# SolarController.net
KiCad netlist of a schematic drawn in EAGLE
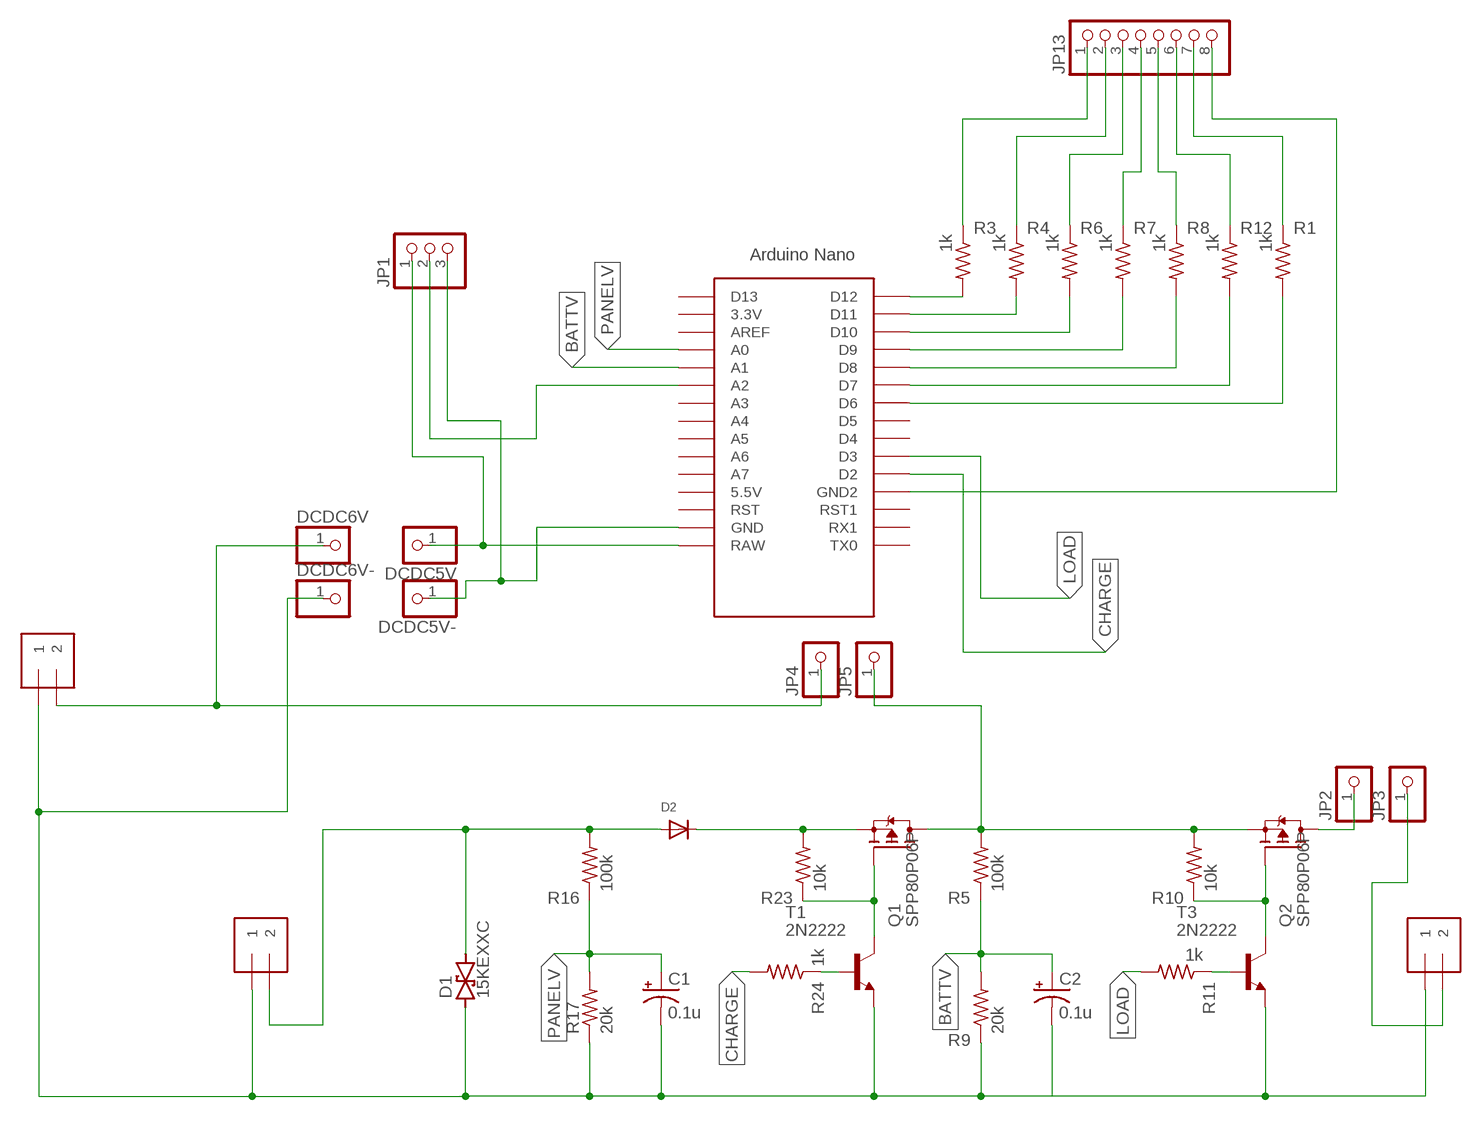
[diagram p0: schematic, sheet 1]

(export (version "E")
  (design (tool "Eeschema 10.0.6"))
  (components
    (comp (ref "BATTERY")
      (value "1X2-3.5MM")
      (footprint "eagle-import:1X2-3.5MM")
      (libsource (lib "eagle-import") (part "1X2-3.5MM"))
    )
    (comp (ref "C1")
      (value "0.1u")
      (footprint "eagle-import:B45181B")
      (libsource (lib "eagle-import") (part "CPOL-USB45181B"))
    )
    (comp (ref "C2")
      (value "0.1u")
      (footprint "eagle-import:B45181B")
      (libsource (lib "eagle-import") (part "CPOL-USB45181B"))
    )
    (comp (ref "D1")
      (value "15KEXXC")
      (footprint "eagle-import:CB429-17")
      (libsource (lib "eagle-import") (part "15KEXXC"))
    )
    (comp (ref "D2")
      (value "DIODEDO-1N4148")
      (footprint "eagle-import:DO-1N4148")
      (libsource (lib "eagle-import") (part "DIODEDO-1N4148"))
    )
    (comp (ref "DCDC5V")
      (value "PINHD-1X1CB")
      (footprint "eagle-import:1X01-CLEANBIG")
      (libsource (lib "eagle-import") (part "PINHD-1X1CB"))
    )
    (comp (ref "DCDC5V-")
      (value "PINHD-1X1CB")
      (footprint "eagle-import:1X01-CLEANBIG")
      (libsource (lib "eagle-import") (part "PINHD-1X1CB"))
    )
    (comp (ref "DCDC6V")
      (value "PINHD-1X1CB")
      (footprint "eagle-import:1X01-CLEANBIG")
      (libsource (lib "eagle-import") (part "PINHD-1X1CB"))
    )
    (comp (ref "DCDC6V-")
      (value "PINHD-1X1CB")
      (footprint "eagle-import:1X01-CLEANBIG")
      (libsource (lib "eagle-import") (part "PINHD-1X1CB"))
    )
    (comp (ref "JP1")
      (value "PINHD-1X3CB")
      (footprint "eagle-import:1X03-CLEANBIG")
      (libsource (lib "eagle-import") (part "PINHD-1X3CB"))
    )
    (comp (ref "JP2")
      (value "PINHD-1X1CB")
      (footprint "eagle-import:1X01-CLEANBIG")
      (libsource (lib "eagle-import") (part "PINHD-1X1CB"))
    )
    (comp (ref "JP3")
      (value "PINHD-1X1CB")
      (footprint "eagle-import:1X01-CLEANBIG")
      (libsource (lib "eagle-import") (part "PINHD-1X1CB"))
    )
    (comp (ref "JP4")
      (value "PINHD-1X1CB")
      (footprint "eagle-import:1X01-CLEANBIG")
      (libsource (lib "eagle-import") (part "PINHD-1X1CB"))
    )
    (comp (ref "JP5")
      (value "PINHD-1X1CB")
      (footprint "eagle-import:1X01-CLEANBIG")
      (libsource (lib "eagle-import") (part "PINHD-1X1CB"))
    )
    (comp (ref "JP13")
      (value "PINHD-1X8BIG")
      (footprint "eagle-import:1X08-BIG")
      (libsource (lib "eagle-import") (part "PINHD-1X8BIG"))
    )
    (comp (ref "LOAD")
      (value "1X2-3.5MM")
      (footprint "eagle-import:1X2-3.5MM")
      (libsource (lib "eagle-import") (part "1X2-3.5MM"))
    )
    (comp (ref "PANEL")
      (value "1X2-3.5MM")
      (footprint "eagle-import:1X2-3.5MM")
      (libsource (lib "eagle-import") (part "1X2-3.5MM"))
    )
    (comp (ref "Q1")
      (value "SPP80P06P")
      (footprint "eagle-import:TO220")
      (libsource (lib "eagle-import") (part "SPP80P06P"))
    )
    (comp (ref "Q2")
      (value "SPP80P06P")
      (footprint "eagle-import:TO220")
      (libsource (lib "eagle-import") (part "SPP80P06P"))
    )
    (comp (ref "R1")
      (value "1k")
      (footprint "eagle-import:0207_9")
      (libsource (lib "eagle-import") (part "R-US_0207/9"))
    )
    (comp (ref "R3")
      (value "1k")
      (footprint "eagle-import:0207_9")
      (libsource (lib "eagle-import") (part "R-US_0207/9"))
    )
    (comp (ref "R4")
      (value "1k")
      (footprint "eagle-import:0207_9")
      (libsource (lib "eagle-import") (part "R-US_0207/9"))
    )
    (comp (ref "R5")
      (value "100k")
      (footprint "eagle-import:0207_9")
      (libsource (lib "eagle-import") (part "R-US_0207/9"))
    )
    (comp (ref "R6")
      (value "1k")
      (footprint "eagle-import:0207_9")
      (libsource (lib "eagle-import") (part "R-US_0207/9"))
    )
    (comp (ref "R7")
      (value "1k")
      (footprint "eagle-import:0207_9")
      (libsource (lib "eagle-import") (part "R-US_0207/9"))
    )
    (comp (ref "R8")
      (value "1k")
      (footprint "eagle-import:0207_9")
      (libsource (lib "eagle-import") (part "R-US_0207/9"))
    )
    (comp (ref "R9")
      (value "20k")
      (footprint "eagle-import:0207_9")
      (libsource (lib "eagle-import") (part "R-US_0207/9"))
    )
    (comp (ref "R10")
      (value "10k")
      (footprint "eagle-import:0207_9")
      (libsource (lib "eagle-import") (part "R-US_0207/9"))
    )
    (comp (ref "R11")
      (value "1k")
      (footprint "eagle-import:0207_9")
      (libsource (lib "eagle-import") (part "R-US_0207/9"))
    )
    (comp (ref "R12")
      (value "1k")
      (footprint "eagle-import:0207_9")
      (libsource (lib "eagle-import") (part "R-US_0207/9"))
    )
    (comp (ref "R16")
      (value "100k")
      (footprint "eagle-import:0207_9")
      (libsource (lib "eagle-import") (part "R-US_0207/9"))
    )
    (comp (ref "R17")
      (value "20k")
      (footprint "eagle-import:0207_9")
      (libsource (lib "eagle-import") (part "R-US_0207/9"))
    )
    (comp (ref "R23")
      (value "10k")
      (footprint "eagle-import:0207_9")
      (libsource (lib "eagle-import") (part "R-US_0207/9"))
    )
    (comp (ref "R24")
      (value "1k")
      (footprint "eagle-import:0207_9")
      (libsource (lib "eagle-import") (part "R-US_0207/9"))
    )
    (comp (ref "T1")
      (value "2N2222")
      (footprint "eagle-import:TO92-EBC-OVAL")
      (libsource (lib "eagle-import") (part "2N2222"))
    )
    (comp (ref "T3")
      (value "2N2222")
      (footprint "eagle-import:TO92-EBC-OVAL")
      (libsource (lib "eagle-import") (part "2N2222"))
    )
    (comp (ref "U$1")
      (value "NANO")
      (footprint "eagle-import:NANO")
      (libsource (lib "eagle-import") (part "NANO"))
    )
  )
  (nets
    (net (code "1") (name "BATTV") (class "Default")
      (node (ref "C2") (pin "+") (pinfunction "+_+") (pintype "passive"))
      (node (ref "R5") (pin "1") (pinfunction "1_1") (pintype "passive"))
      (node (ref "R9") (pin "2") (pinfunction "2_2") (pintype "passive"))
      (node (ref "U$1") (pin "A1") (pinfunction "A1_A1") (pintype "bidirectional"))
    )
    (net (code "2") (name "CHARGE") (class "Default")
      (node (ref "R24") (pin "2") (pinfunction "2_2") (pintype "passive"))
      (node (ref "U$1") (pin "D2") (pinfunction "D2_D2") (pintype "bidirectional"))
    )
    (net (code "3") (name "LOAD") (class "Default")
      (node (ref "R11") (pin "2") (pinfunction "2_2") (pintype "passive"))
      (node (ref "U$1") (pin "D3") (pinfunction "D3_D3") (pintype "bidirectional"))
    )
    (net (code "4") (name "Net-(BATTERY-Pad2)") (class "Default")
      (node (ref "BATTERY") (pin "2") (pinfunction "2_2") (pintype "passive"))
      (node (ref "DCDC6V") (pin "1") (pinfunction "1_1") (pintype "passive"))
      (node (ref "JP4") (pin "1") (pinfunction "1_1") (pintype "passive"))
    )
    (net (code "5") (name "Net-(D1-1)") (class "Default")
      (node (ref "BATTERY") (pin "1") (pinfunction "1_1") (pintype "passive"))
      (node (ref "C1") (pin "-") (pinfunction "-_-") (pintype "passive"))
      (node (ref "C2") (pin "-") (pinfunction "-_-") (pintype "passive"))
      (node (ref "D1") (pin "A") (pinfunction "1_A") (pintype "passive"))
      (node (ref "DCDC6V-") (pin "1") (pinfunction "1_1") (pintype "passive"))
      (node (ref "LOAD") (pin "1") (pinfunction "1_1") (pintype "passive"))
      (node (ref "PANEL") (pin "1") (pinfunction "1_1") (pintype "passive"))
      (node (ref "R17") (pin "1") (pinfunction "1_1") (pintype "passive"))
      (node (ref "R9") (pin "1") (pinfunction "1_1") (pintype "passive"))
      (node (ref "T1") (pin "E") (pinfunction "E_E") (pintype "passive"))
      (node (ref "T3") (pin "E") (pinfunction "E_E") (pintype "passive"))
    )
    (net (code "6") (name "Net-(D1-2)") (class "Default")
      (node (ref "D1") (pin "C") (pinfunction "2_C") (pintype "passive"))
      (node (ref "D2") (pin "A") (pinfunction "A_A") (pintype "passive"))
      (node (ref "PANEL") (pin "2") (pinfunction "2_2") (pintype "passive"))
      (node (ref "R16") (pin "2") (pinfunction "2_2") (pintype "passive"))
    )
    (net (code "7") (name "Net-(DCDC5V--Pad1)") (class "Default")
      (node (ref "DCDC5V-") (pin "1") (pinfunction "1_1") (pintype "passive"))
      (node (ref "JP1") (pin "3") (pinfunction "3_3") (pintype "passive"))
      (node (ref "U$1") (pin "GND") (pinfunction "GND_GND") (pintype "bidirectional"))
    )
    (net (code "8") (name "Net-(DCDC5V-Pad1)") (class "Default")
      (node (ref "DCDC5V") (pin "1") (pinfunction "1_1") (pintype "passive"))
      (node (ref "JP1") (pin "1") (pinfunction "1_1") (pintype "passive"))
      (node (ref "U$1") (pin "RAW") (pinfunction "RAW_RAW") (pintype "bidirectional"))
    )
    (net (code "9") (name "Net-(JP1-Pad2)") (class "Default")
      (node (ref "JP1") (pin "2") (pinfunction "2_2") (pintype "passive"))
      (node (ref "U$1") (pin "A2") (pinfunction "A2_A2") (pintype "bidirectional"))
    )
    (net (code "10") (name "Net-(JP3-Pad1)") (class "Default")
      (node (ref "JP3") (pin "1") (pinfunction "1_1") (pintype "passive"))
      (node (ref "LOAD") (pin "2") (pinfunction "2_2") (pintype "passive"))
    )
    (net (code "11") (name "Net-(JP13-Pad1)") (class "Default")
      (node (ref "JP13") (pin "1") (pinfunction "1_1") (pintype "passive"))
      (node (ref "R3") (pin "1") (pinfunction "1_1") (pintype "passive"))
    )
    (net (code "12") (name "Net-(JP13-Pad2)") (class "Default")
      (node (ref "JP13") (pin "2") (pinfunction "2_2") (pintype "passive"))
      (node (ref "R4") (pin "1") (pinfunction "1_1") (pintype "passive"))
    )
    (net (code "13") (name "Net-(JP13-Pad3)") (class "Default")
      (node (ref "JP13") (pin "3") (pinfunction "3_3") (pintype "passive"))
      (node (ref "R6") (pin "1") (pinfunction "1_1") (pintype "passive"))
    )
    (net (code "14") (name "Net-(JP13-Pad4)") (class "Default")
      (node (ref "JP13") (pin "4") (pinfunction "4_4") (pintype "passive"))
      (node (ref "R7") (pin "1") (pinfunction "1_1") (pintype "passive"))
    )
    (net (code "15") (name "Net-(JP13-Pad5)") (class "Default")
      (node (ref "JP13") (pin "5") (pinfunction "5_5") (pintype "passive"))
      (node (ref "R8") (pin "1") (pinfunction "1_1") (pintype "passive"))
    )
    (net (code "16") (name "Net-(JP13-Pad6)") (class "Default")
      (node (ref "JP13") (pin "6") (pinfunction "6_6") (pintype "passive"))
      (node (ref "R12") (pin "1") (pinfunction "1_1") (pintype "passive"))
    )
    (net (code "17") (name "Net-(JP13-Pad7)") (class "Default")
      (node (ref "JP13") (pin "7") (pinfunction "7_7") (pintype "passive"))
      (node (ref "R1") (pin "1") (pinfunction "1_1") (pintype "passive"))
    )
    (net (code "18") (name "Net-(Q1-D)") (class "Default")
      (node (ref "JP5") (pin "1") (pinfunction "1_1") (pintype "passive"))
      (node (ref "Q1") (pin "2") (pinfunction "D_2") (pintype "passive"))
      (node (ref "Q2") (pin "3") (pinfunction "S_3") (pintype "passive"))
      (node (ref "R10") (pin "2") (pinfunction "2_2") (pintype "passive"))
      (node (ref "R5") (pin "2") (pinfunction "2_2") (pintype "passive"))
    )
    (net (code "19") (name "Net-(Q1-G)") (class "Default")
      (node (ref "Q1") (pin "1") (pinfunction "G_1") (pintype "passive"))
      (node (ref "R23") (pin "1") (pinfunction "1_1") (pintype "passive"))
      (node (ref "T1") (pin "C") (pinfunction "C_C") (pintype "passive"))
    )
    (net (code "20") (name "Net-(Q1-S)") (class "Default")
      (node (ref "D2") (pin "C") (pinfunction "C_C") (pintype "passive"))
      (node (ref "Q1") (pin "3") (pinfunction "S_3") (pintype "passive"))
      (node (ref "R23") (pin "2") (pinfunction "2_2") (pintype "passive"))
    )
    (net (code "21") (name "Net-(Q2-D)") (class "Default")
      (node (ref "JP2") (pin "1") (pinfunction "1_1") (pintype "passive"))
      (node (ref "Q2") (pin "2") (pinfunction "D_2") (pintype "passive"))
    )
    (net (code "22") (name "Net-(Q2-G)") (class "Default")
      (node (ref "Q2") (pin "1") (pinfunction "G_1") (pintype "passive"))
      (node (ref "R10") (pin "1") (pinfunction "1_1") (pintype "passive"))
      (node (ref "T3") (pin "C") (pinfunction "C_C") (pintype "passive"))
    )
    (net (code "23") (name "Net-(R1-Pad2)") (class "Default")
      (node (ref "R1") (pin "2") (pinfunction "2_2") (pintype "passive"))
      (node (ref "U$1") (pin "D6") (pinfunction "D6_D6") (pintype "bidirectional"))
    )
    (net (code "24") (name "Net-(R3-Pad2)") (class "Default")
      (node (ref "R3") (pin "2") (pinfunction "2_2") (pintype "passive"))
      (node (ref "U$1") (pin "D12") (pinfunction "D12_D12") (pintype "bidirectional"))
    )
    (net (code "25") (name "Net-(R4-Pad2)") (class "Default")
      (node (ref "R4") (pin "2") (pinfunction "2_2") (pintype "passive"))
      (node (ref "U$1") (pin "D11") (pinfunction "D11_D11") (pintype "bidirectional"))
    )
    (net (code "26") (name "Net-(R6-Pad2)") (class "Default")
      (node (ref "R6") (pin "2") (pinfunction "2_2") (pintype "passive"))
      (node (ref "U$1") (pin "D10") (pinfunction "D10_D10") (pintype "bidirectional"))
    )
    (net (code "27") (name "Net-(R7-Pad2)") (class "Default")
      (node (ref "R7") (pin "2") (pinfunction "2_2") (pintype "passive"))
      (node (ref "U$1") (pin "D9") (pinfunction "D9_D9") (pintype "bidirectional"))
    )
    (net (code "28") (name "Net-(R8-Pad2)") (class "Default")
      (node (ref "R8") (pin "2") (pinfunction "2_2") (pintype "passive"))
      (node (ref "U$1") (pin "D8") (pinfunction "D8_D8") (pintype "bidirectional"))
    )
    (net (code "29") (name "Net-(R11-Pad1)") (class "Default")
      (node (ref "R11") (pin "1") (pinfunction "1_1") (pintype "passive"))
      (node (ref "T3") (pin "B") (pinfunction "B_B") (pintype "passive"))
    )
    (net (code "30") (name "Net-(R12-Pad2)") (class "Default")
      (node (ref "R12") (pin "2") (pinfunction "2_2") (pintype "passive"))
      (node (ref "U$1") (pin "D7") (pinfunction "D7_D7") (pintype "bidirectional"))
    )
    (net (code "31") (name "Net-(R24-Pad1)") (class "Default")
      (node (ref "R24") (pin "1") (pinfunction "1_1") (pintype "passive"))
      (node (ref "T1") (pin "B") (pinfunction "B_B") (pintype "passive"))
    )
    (net (code "32") (name "Net-(U$1-GND2)") (class "Default")
      (node (ref "JP13") (pin "8") (pinfunction "8_8") (pintype "passive"))
      (node (ref "U$1") (pin "GND1") (pinfunction "GND2_GND1") (pintype "bidirectional"))
    )
    (net (code "33") (name "PANELV") (class "Default")
      (node (ref "C1") (pin "+") (pinfunction "+_+") (pintype "passive"))
      (node (ref "R16") (pin "1") (pinfunction "1_1") (pintype "passive"))
      (node (ref "R17") (pin "2") (pinfunction "2_2") (pintype "passive"))
    )
    (net (code "34") (name "unconnected-(U$1-5.5V-Pad5V)") (class "Default")
      (node (ref "U$1") (pin "5V") (pinfunction "5.5V_5V") (pintype "bidirectional"))
    )
    (net (code "35") (name "unconnected-(U$1-Pad3.3V)") (class "Default")
      (node (ref "U$1") (pin "3.3V") (pinfunction "3.3V_3.3V") (pintype "bidirectional"))
    )
    (net (code "36") (name "unconnected-(U$1-PadA0)") (class "Default")
      (node (ref "U$1") (pin "A0") (pinfunction "A0_A0") (pintype "bidirectional"))
    )
    (net (code "37") (name "unconnected-(U$1-PadA3)") (class "Default")
      (node (ref "U$1") (pin "A3") (pinfunction "A3_A3") (pintype "bidirectional"))
    )
    (net (code "38") (name "unconnected-(U$1-PadA4)") (class "Default")
      (node (ref "U$1") (pin "A4") (pinfunction "A4_A4") (pintype "bidirectional"))
    )
    (net (code "39") (name "unconnected-(U$1-PadA5)") (class "Default")
      (node (ref "U$1") (pin "A5") (pinfunction "A5_A5") (pintype "bidirectional"))
    )
    (net (code "40") (name "unconnected-(U$1-PadA6)") (class "Default")
      (node (ref "U$1") (pin "A6") (pinfunction "A6_A6") (pintype "bidirectional"))
    )
    (net (code "41") (name "unconnected-(U$1-PadA7)") (class "Default")
      (node (ref "U$1") (pin "A7") (pinfunction "A7_A7") (pintype "bidirectional"))
    )
    (net (code "42") (name "unconnected-(U$1-PadAREF)") (class "Default")
      (node (ref "U$1") (pin "AREF") (pinfunction "AREF_AREF") (pintype "bidirectional"))
    )
    (net (code "43") (name "unconnected-(U$1-PadD4)") (class "Default")
      (node (ref "U$1") (pin "D4") (pinfunction "D4_D4") (pintype "bidirectional"))
    )
    (net (code "44") (name "unconnected-(U$1-PadD5)") (class "Default")
      (node (ref "U$1") (pin "D5") (pinfunction "D5_D5") (pintype "bidirectional"))
    )
    (net (code "45") (name "unconnected-(U$1-PadD13)") (class "Default")
      (node (ref "U$1") (pin "D13") (pinfunction "D13_D13") (pintype "bidirectional"))
    )
    (net (code "46") (name "unconnected-(U$1-PadICSP1)") (class "Default")
      (node (ref "U$1") (pin "ICSP1") (pinfunction "ICSP1_ICSP1") (pintype "bidirectional"))
    )
    (net (code "47") (name "unconnected-(U$1-PadICSP2)") (class "Default")
      (node (ref "U$1") (pin "ICSP2") (pinfunction "ICSP2_ICSP2") (pintype "bidirectional"))
    )
    (net (code "48") (name "unconnected-(U$1-PadICSP3)") (class "Default")
      (node (ref "U$1") (pin "ICSP3") (pinfunction "ICSP3_ICSP3") (pintype "bidirectional"))
    )
    (net (code "49") (name "unconnected-(U$1-PadICSP4)") (class "Default")
      (node (ref "U$1") (pin "ICSP4") (pinfunction "ICSP4_ICSP4") (pintype "bidirectional"))
    )
    (net (code "50") (name "unconnected-(U$1-PadICSP5)") (class "Default")
      (node (ref "U$1") (pin "ICSP5") (pinfunction "ICSP5_ICSP5") (pintype "bidirectional"))
    )
    (net (code "51") (name "unconnected-(U$1-PadICSP6)") (class "Default")
      (node (ref "U$1") (pin "ICSP6") (pinfunction "ICSP6_ICSP6") (pintype "bidirectional"))
    )
    (net (code "52") (name "unconnected-(U$1-PadRST)") (class "Default")
      (node (ref "U$1") (pin "RST") (pinfunction "RST_RST") (pintype "bidirectional"))
    )
    (net (code "53") (name "unconnected-(U$1-PadRST1)") (class "Default")
      (node (ref "U$1") (pin "RST1") (pinfunction "RST1_RST1") (pintype "bidirectional"))
    )
    (net (code "54") (name "unconnected-(U$1-PadRX1)") (class "Default")
      (node (ref "U$1") (pin "RX1") (pinfunction "RX1_RX1") (pintype "bidirectional"))
    )
    (net (code "55") (name "unconnected-(U$1-PadTX0)") (class "Default")
      (node (ref "U$1") (pin "TX0") (pinfunction "TX0_TX0") (pintype "bidirectional"))
    )
  )
)
